# encoder.net
KiCad netlist of a schematic drawn in Altium Designer
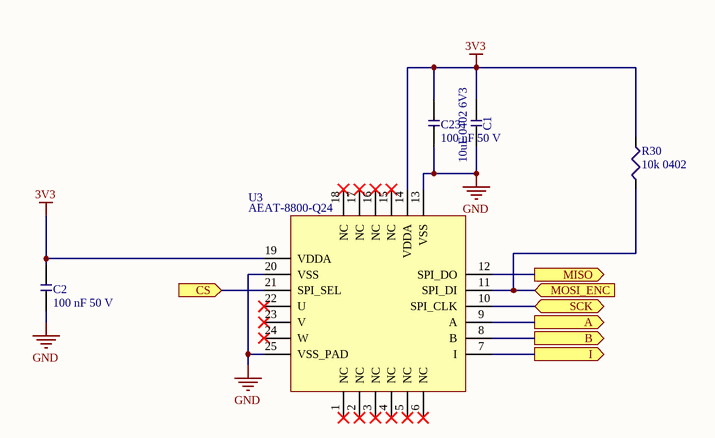
[diagram p0: encoder.SchDoc]

(export (version "E")
  (design (tool "Eeschema 10.0.6"))
  (components
    (comp (ref "C1")
      (value "10uF 0402 6V3")
      (footprint "CAP_0402")
      (description "10uF 20% 0402 6V3 X6S")
      (fields (field (name "TOLERANCE") "20%") (field (name "VOLTAGE") "6V3"))
      (libsource (lib "ON Development Vault") (part "Capacitor"))
    )
    (comp (ref "C2")
      (value "100 nF 50 V")
      (footprint "CAP_0402")
      (description "Multilayer Ceramic Capacitors MLCC - SMD/SMT .1uF 50Volts X7R +/-10% 0402 STD")
      (fields (field (name "TOLERANCE") "10%") (field (name "VOLTAGE") "50 V"))
      (libsource (lib "ON Development Vault") (part "Capacitor"))
    )
    (comp (ref "C23")
      (value "100 nF 50 V")
      (footprint "CAP_0402")
      (description "Multilayer Ceramic Capacitors MLCC - SMD/SMT .1uF 50Volts X7R +/-10% 0402 STD")
      (fields (field (name "TOLERANCE") "10%") (field (name "VOLTAGE") "50 V"))
      (libsource (lib "ON Development Vault") (part "Capacitor"))
    )
    (comp (ref "R30")
      (value "10k 0402")
      (footprint "RES_0402")
      (description "RES SMD 10K OHM 1% 1/16W 0402")
      (fields (field (name "POWER") "1/16 W") (field (name "TOLERANCE") "1 %"))
      (libsource (lib "ON Development Vault") (part "Resistor"))
    )
    (comp (ref "U3")
      (value "AEAT-8800-Q24")
      (footprint "AEAT-8800-Q24")
      (description "16-BIT PROG ANG ENCODER")
      (libsource (lib "ON Development Vault") (part "AEAT-8800-Q24"))
    )
  )
  (nets
    (net (code "1") (name "/A") (class "Default")
      (node (ref "U3") (pin "9") (pinfunction "A_9") (pintype "passive"))
    )
    (net (code "2") (name "/B") (class "Default")
      (node (ref "U3") (pin "8") (pinfunction "B_8") (pintype "passive"))
    )
    (net (code "3") (name "/CS") (class "Default")
      (node (ref "U3") (pin "21") (pinfunction "SPI_SEL_21") (pintype "passive"))
    )
    (net (code "4") (name "/I") (class "Default")
      (node (ref "U3") (pin "7") (pinfunction "I_7") (pintype "passive"))
    )
    (net (code "5") (name "/MISO") (class "Default")
      (node (ref "U3") (pin "12") (pinfunction "SPI_DO_12") (pintype "passive"))
    )
    (net (code "6") (name "/MOSI_ENC") (class "Default")
      (node (ref "R30") (pin "1") (pinfunction "1_1") (pintype "passive"))
      (node (ref "U3") (pin "11") (pinfunction "SPI_DI_11") (pintype "passive"))
    )
    (net (code "7") (name "/SCK") (class "Default")
      (node (ref "U3") (pin "10") (pinfunction "SPI_CLK_10") (pintype "passive"))
    )
    (net (code "8") (name "3V3") (class "Default")
      (node (ref "C1") (pin "2") (pinfunction "2_2") (pintype "passive"))
      (node (ref "C2") (pin "1") (pinfunction "1_1") (pintype "passive"))
      (node (ref "C23") (pin "1") (pinfunction "1_1") (pintype "passive"))
      (node (ref "R30") (pin "2") (pinfunction "2_2") (pintype "passive"))
      (node (ref "U3") (pin "14") (pinfunction "VDDA_14") (pintype "passive"))
      (node (ref "U3") (pin "19") (pinfunction "VDDA_19") (pintype "passive"))
    )
    (net (code "9") (name "GND") (class "Default")
      (node (ref "C1") (pin "1") (pinfunction "1_1") (pintype "passive"))
      (node (ref "C2") (pin "2") (pinfunction "2_2") (pintype "passive"))
      (node (ref "C23") (pin "2") (pinfunction "2_2") (pintype "passive"))
      (node (ref "U3") (pin "13") (pinfunction "VSS_13") (pintype "passive"))
      (node (ref "U3") (pin "20") (pinfunction "VSS_20") (pintype "passive"))
      (node (ref "U3") (pin "25") (pinfunction "VSS_PAD_25") (pintype "passive"))
    )
    (net (code "10") (name "unconnected-(U3-NC-Pad1)") (class "Default")
      (node (ref "U3") (pin "1") (pinfunction "NC_1") (pintype "passive+no_connect"))
    )
    (net (code "11") (name "unconnected-(U3-NC-Pad2)") (class "Default")
      (node (ref "U3") (pin "2") (pinfunction "NC_2") (pintype "passive+no_connect"))
    )
    (net (code "12") (name "unconnected-(U3-NC-Pad3)") (class "Default")
      (node (ref "U3") (pin "3") (pinfunction "NC_3") (pintype "passive+no_connect"))
    )
    (net (code "13") (name "unconnected-(U3-NC-Pad4)") (class "Default")
      (node (ref "U3") (pin "4") (pinfunction "NC_4") (pintype "passive+no_connect"))
    )
    (net (code "14") (name "unconnected-(U3-NC-Pad5)") (class "Default")
      (node (ref "U3") (pin "5") (pinfunction "NC_5") (pintype "passive+no_connect"))
    )
    (net (code "15") (name "unconnected-(U3-NC-Pad6)") (class "Default")
      (node (ref "U3") (pin "6") (pinfunction "NC_6") (pintype "passive+no_connect"))
    )
    (net (code "16") (name "unconnected-(U3-NC-Pad15)") (class "Default")
      (node (ref "U3") (pin "15") (pinfunction "NC_15") (pintype "passive+no_connect"))
    )
    (net (code "17") (name "unconnected-(U3-NC-Pad16)") (class "Default")
      (node (ref "U3") (pin "16") (pinfunction "NC_16") (pintype "passive+no_connect"))
    )
    (net (code "18") (name "unconnected-(U3-NC-Pad17)") (class "Default")
      (node (ref "U3") (pin "17") (pinfunction "NC_17") (pintype "passive+no_connect"))
    )
    (net (code "19") (name "unconnected-(U3-NC-Pad18)") (class "Default")
      (node (ref "U3") (pin "18") (pinfunction "NC_18") (pintype "passive+no_connect"))
    )
    (net (code "20") (name "unconnected-(U3-U-Pad22)") (class "Default")
      (node (ref "U3") (pin "22") (pinfunction "U_22") (pintype "passive+no_connect"))
    )
    (net (code "21") (name "unconnected-(U3-V-Pad23)") (class "Default")
      (node (ref "U3") (pin "23") (pinfunction "V_23") (pintype "passive+no_connect"))
    )
    (net (code "22") (name "unconnected-(U3-W-Pad24)") (class "Default")
      (node (ref "U3") (pin "24") (pinfunction "W_24") (pintype "passive+no_connect"))
    )
  )
)
